# Cleanroom_Nano.net
KiCad netlist of a schematic drawn in EAGLE
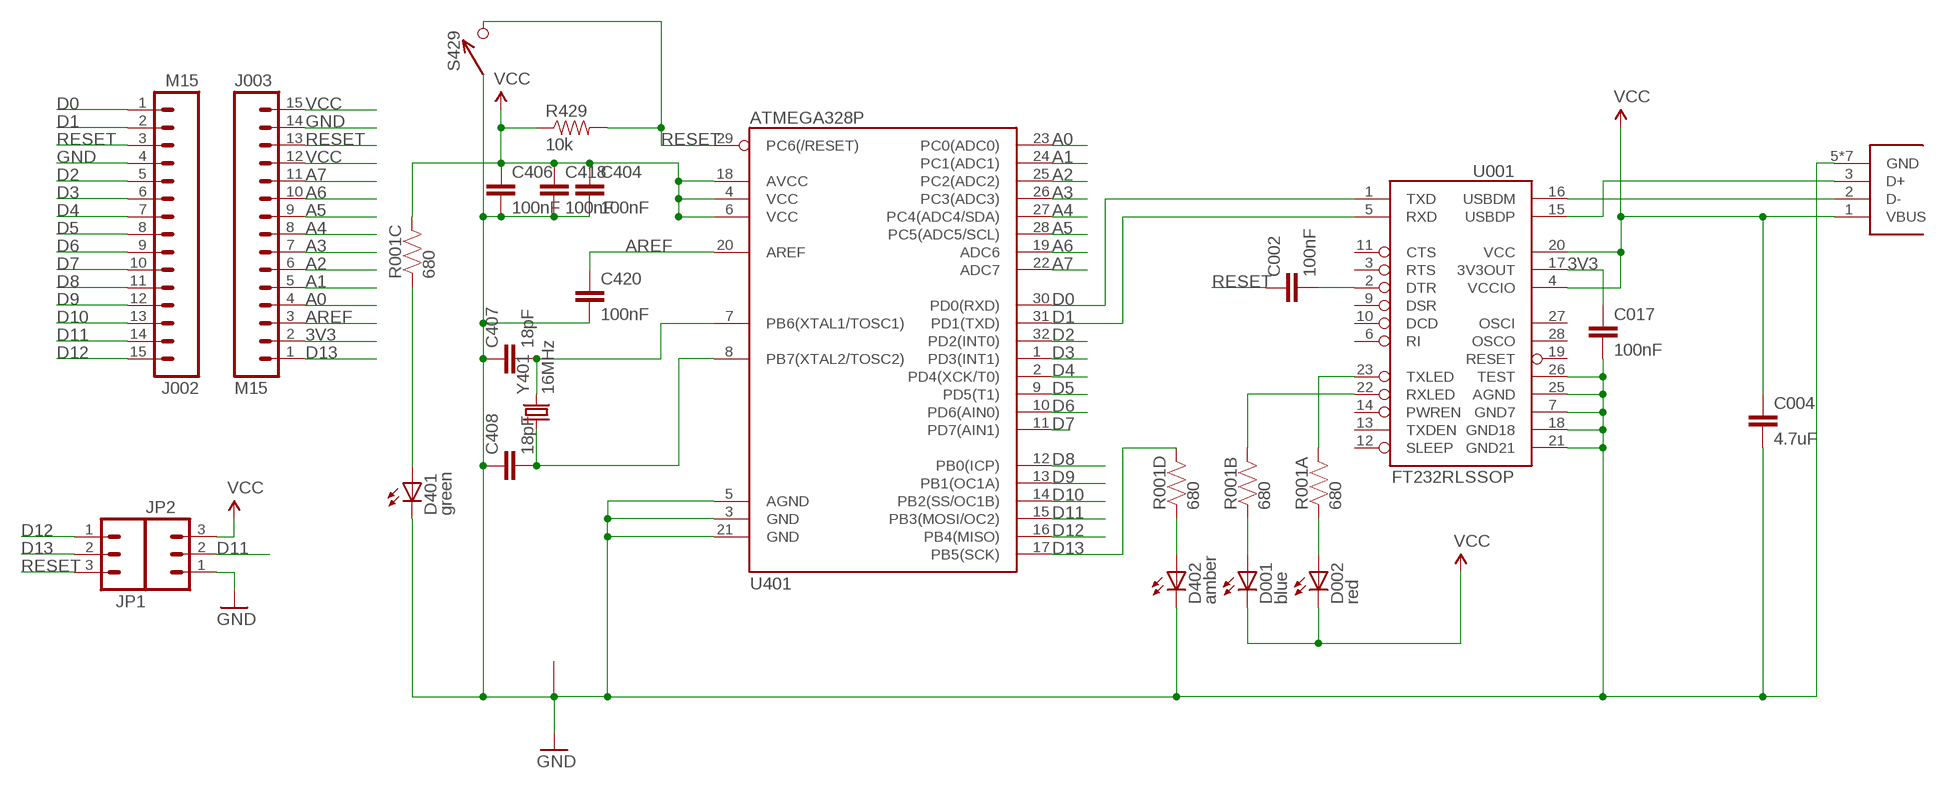
[diagram p0: schematic, sheet 1]

(export (version "E")
  (design (tool "Eeschema 10.0.6"))
  (components
    (comp (ref "C002")
      (value "100nF")
      (footprint "eagle-import:0402-CAP")
      (libsource (lib "eagle-import") (part "CAP0402-CAP"))
    )
    (comp (ref "C004")
      (value "4.7uF")
      (footprint "eagle-import:0402-CAP")
      (libsource (lib "eagle-import") (part "CAP0402-CAP"))
    )
    (comp (ref "C017")
      (value "100nF")
      (footprint "eagle-import:0402-CAP")
      (libsource (lib "eagle-import") (part "CAP0402-CAP"))
    )
    (comp (ref "C404")
      (value "100nF")
      (footprint "eagle-import:0402-CAP")
      (libsource (lib "eagle-import") (part "CAP0402-CAP"))
    )
    (comp (ref "C406")
      (value "100nF")
      (footprint "eagle-import:0402-CAP")
      (libsource (lib "eagle-import") (part "CAP0402-CAP"))
    )
    (comp (ref "C407")
      (value "18pF")
      (footprint "eagle-import:0402-CAP")
      (libsource (lib "eagle-import") (part "CAP0402-CAP"))
    )
    (comp (ref "C408")
      (value "18pF")
      (footprint "eagle-import:0402-CAP")
      (libsource (lib "eagle-import") (part "CAP0402-CAP"))
    )
    (comp (ref "C418")
      (value "100nF")
      (footprint "eagle-import:0402-CAP")
      (libsource (lib "eagle-import") (part "CAP0402-CAP"))
    )
    (comp (ref "C420")
      (value "100nF")
      (footprint "eagle-import:0402-CAP")
      (libsource (lib "eagle-import") (part "CAP0402-CAP"))
    )
    (comp (ref "D001")
      (value "blue")
      (footprint "eagle-import:LED-0603")
      (libsource (lib "eagle-import") (part "LED0603"))
    )
    (comp (ref "D002")
      (value "red")
      (footprint "eagle-import:LED-0603")
      (libsource (lib "eagle-import") (part "LED0603"))
    )
    (comp (ref "D401")
      (value "green")
      (footprint "eagle-import:LED-0603")
      (libsource (lib "eagle-import") (part "LED0603"))
    )
    (comp (ref "D402")
      (value "amber")
      (footprint "eagle-import:LED-0603")
      (libsource (lib "eagle-import") (part "LED0603"))
    )
    (comp (ref "J001")
      (value "USB_MICROB_JST")
      (footprint "eagle-import:UB-MC5BR3-SD204-4S")
      (libsource (lib "eagle-import") (part "USB_MICROB_JST"))
    )
    (comp (ref "J002")
      (value "M15")
      (footprint "eagle-import:1X15")
      (libsource (lib "eagle-import") (part "M15"))
    )
    (comp (ref "J003")
      (value "M15")
      (footprint "eagle-import:1X15")
      (libsource (lib "eagle-import") (part "M15"))
    )
    (comp (ref "JP1")
      (value "M03PTH")
      (footprint "eagle-import:1X03")
      (libsource (lib "eagle-import") (part "M03PTH"))
    )
    (comp (ref "JP2")
      (value "M03PTH")
      (footprint "eagle-import:1X03")
      (libsource (lib "eagle-import") (part "M03PTH"))
    )
    (comp (ref "R001")
      (value "680")
      (footprint "eagle-import:CRA04")
      (libsource (lib "eagle-import") (part "RP404"))
    )
    (comp (ref "R429")
      (value "10k")
      (footprint "eagle-import:0402-RES")
      (libsource (lib "eagle-import") (part "RESISTOR0402-RES"))
    )
    (comp (ref "S429")
      (value "B3U-1000P")
      (footprint "eagle-import:B3U-1000P")
      (libsource (lib "eagle-import") (part "B3U-1000P"))
    )
    (comp (ref "U001")
      (value "FT232RLSSOP")
      (footprint "eagle-import:SSOP28DB")
      (libsource (lib "eagle-import") (part "FT232RLSSOP"))
    )
    (comp (ref "U401")
      (value "ATMEGA328P")
      (footprint "eagle-import:TQFP32-08")
      (libsource (lib "eagle-import") (part "ATMEGA168"))
    )
    (comp (ref "Y401")
      (value "16MHz")
      (footprint "eagle-import:CRYSTAL_SMD_2MM_2_5MM")
      (libsource (lib "eagle-import") (part "CX2520"))
    )
  )
  (nets
    (net (code "1") (name "/3V3") (class "Default")
      (node (ref "C017") (pin "1") (pinfunction "1_1") (pintype "passive"))
      (node (ref "J003") (pin "2") (pinfunction "2_2") (pintype "passive"))
      (node (ref "U001") (pin "17") (pinfunction "3V3OUT_17") (pintype "output"))
    )
    (net (code "2") (name "/A0") (class "Default")
      (node (ref "J003") (pin "4") (pinfunction "4_4") (pintype "passive"))
      (node (ref "U401") (pin "23") (pinfunction "PC0(ADC0)_23") (pintype "bidirectional"))
    )
    (net (code "3") (name "/A1") (class "Default")
      (node (ref "J003") (pin "5") (pinfunction "5_5") (pintype "passive"))
      (node (ref "U401") (pin "24") (pinfunction "PC1(ADC1)_24") (pintype "bidirectional"))
    )
    (net (code "4") (name "/A2") (class "Default")
      (node (ref "J003") (pin "6") (pinfunction "6_6") (pintype "passive"))
      (node (ref "U401") (pin "25") (pinfunction "PC2(ADC2)_25") (pintype "bidirectional"))
    )
    (net (code "5") (name "/A3") (class "Default")
      (node (ref "J003") (pin "7") (pinfunction "7_7") (pintype "passive"))
      (node (ref "U401") (pin "26") (pinfunction "PC3(ADC3)_26") (pintype "bidirectional"))
    )
    (net (code "6") (name "/A4") (class "Default")
      (node (ref "J003") (pin "8") (pinfunction "8_8") (pintype "passive"))
      (node (ref "U401") (pin "27") (pinfunction "PC4(ADC4/SDA)_27") (pintype "bidirectional"))
    )
    (net (code "7") (name "/A5") (class "Default")
      (node (ref "J003") (pin "9") (pinfunction "9_9") (pintype "passive"))
      (node (ref "U401") (pin "28") (pinfunction "PC5(ADC5/SCL)_28") (pintype "bidirectional"))
    )
    (net (code "8") (name "/A6") (class "Default")
      (node (ref "J003") (pin "10") (pinfunction "10_10") (pintype "passive"))
      (node (ref "U401") (pin "19") (pinfunction "ADC6_19") (pintype "bidirectional"))
    )
    (net (code "9") (name "/A7") (class "Default")
      (node (ref "J003") (pin "11") (pinfunction "11_11") (pintype "passive"))
      (node (ref "U401") (pin "22") (pinfunction "ADC7_22") (pintype "bidirectional"))
    )
    (net (code "10") (name "/AREF") (class "Default")
      (node (ref "C420") (pin "1") (pinfunction "1_1") (pintype "passive"))
      (node (ref "J003") (pin "3") (pinfunction "3_3") (pintype "passive"))
      (node (ref "U401") (pin "20") (pinfunction "AREF_20") (pintype "bidirectional"))
    )
    (net (code "11") (name "/D0") (class "Default")
      (node (ref "J002") (pin "1") (pinfunction "1_1") (pintype "passive"))
      (node (ref "U001") (pin "1") (pinfunction "TXD_1") (pintype "output"))
      (node (ref "U401") (pin "30") (pinfunction "PD0(RXD)_30") (pintype "bidirectional"))
    )
    (net (code "12") (name "/D1") (class "Default")
      (node (ref "J002") (pin "2") (pinfunction "2_2") (pintype "passive"))
      (node (ref "U001") (pin "5") (pinfunction "RXD_5") (pintype "input"))
      (node (ref "U401") (pin "31") (pinfunction "PD1(TXD)_31") (pintype "bidirectional"))
    )
    (net (code "13") (name "/D2") (class "Default")
      (node (ref "J002") (pin "5") (pinfunction "5_5") (pintype "passive"))
      (node (ref "U401") (pin "32") (pinfunction "PD2(INT0)_32") (pintype "bidirectional"))
    )
    (net (code "14") (name "/D3") (class "Default")
      (node (ref "J002") (pin "6") (pinfunction "6_6") (pintype "passive"))
      (node (ref "U401") (pin "1") (pinfunction "PD3(INT1)_1") (pintype "bidirectional"))
    )
    (net (code "15") (name "/D4") (class "Default")
      (node (ref "J002") (pin "7") (pinfunction "7_7") (pintype "passive"))
      (node (ref "U401") (pin "2") (pinfunction "PD4(XCK/T0)_2") (pintype "bidirectional"))
    )
    (net (code "16") (name "/D5") (class "Default")
      (node (ref "J002") (pin "8") (pinfunction "8_8") (pintype "passive"))
      (node (ref "U401") (pin "9") (pinfunction "PD5(T1)_9") (pintype "bidirectional"))
    )
    (net (code "17") (name "/D6") (class "Default")
      (node (ref "J002") (pin "9") (pinfunction "9_9") (pintype "passive"))
      (node (ref "U401") (pin "10") (pinfunction "PD6(AIN0)_10") (pintype "bidirectional"))
    )
    (net (code "18") (name "/D7") (class "Default")
      (node (ref "J002") (pin "10") (pinfunction "10_10") (pintype "passive"))
      (node (ref "U401") (pin "11") (pinfunction "PD7(AIN1)_11") (pintype "bidirectional"))
    )
    (net (code "19") (name "/D8") (class "Default")
      (node (ref "J002") (pin "11") (pinfunction "11_11") (pintype "passive"))
      (node (ref "U401") (pin "12") (pinfunction "PB0(ICP)_12") (pintype "bidirectional"))
    )
    (net (code "20") (name "/D9") (class "Default")
      (node (ref "J002") (pin "12") (pinfunction "12_12") (pintype "passive"))
      (node (ref "U401") (pin "13") (pinfunction "PB1(OC1A)_13") (pintype "bidirectional"))
    )
    (net (code "21") (name "/D10") (class "Default")
      (node (ref "J002") (pin "13") (pinfunction "13_13") (pintype "passive"))
      (node (ref "U401") (pin "14") (pinfunction "PB2(SS/OC1B)_14") (pintype "bidirectional"))
    )
    (net (code "22") (name "/D11") (class "Default")
      (node (ref "J002") (pin "14") (pinfunction "14_14") (pintype "passive"))
      (node (ref "JP2") (pin "2") (pinfunction "2_2") (pintype "passive"))
      (node (ref "U401") (pin "15") (pinfunction "PB3(MOSI/OC2)_15") (pintype "bidirectional"))
    )
    (net (code "23") (name "/D12") (class "Default")
      (node (ref "J002") (pin "15") (pinfunction "15_15") (pintype "passive"))
      (node (ref "JP1") (pin "1") (pinfunction "1_1") (pintype "passive"))
      (node (ref "U401") (pin "16") (pinfunction "PB4(MISO)_16") (pintype "bidirectional"))
    )
    (net (code "24") (name "/D13") (class "Default")
      (node (ref "J003") (pin "1") (pinfunction "1_1") (pintype "passive"))
      (node (ref "JP1") (pin "2") (pinfunction "2_2") (pintype "passive"))
      (node (ref "R001") (pin "5") (pinfunction "2_5") (pintype "passive"))
      (node (ref "U401") (pin "17") (pinfunction "PB5(SCK)_17") (pintype "bidirectional"))
    )
    (net (code "25") (name "/RESET") (class "Default")
      (node (ref "C002") (pin "1") (pinfunction "1_1") (pintype "passive"))
      (node (ref "J002") (pin "3") (pinfunction "3_3") (pintype "passive"))
      (node (ref "J003") (pin "13") (pinfunction "13_13") (pintype "passive"))
      (node (ref "JP1") (pin "3") (pinfunction "3_3") (pintype "passive"))
      (node (ref "R429") (pin "2") (pinfunction "2_2") (pintype "passive"))
      (node (ref "S429") (pin "P$2") (pinfunction "2_P$2") (pintype "bidirectional"))
      (node (ref "U401") (pin "29") (pinfunction "PC6(/RESET)_29") (pintype "bidirectional"))
    )
    (net (code "26") (name "GND") (class "Default")
      (node (ref "C004") (pin "2") (pinfunction "2_2") (pintype "passive"))
      (node (ref "C017") (pin "2") (pinfunction "2_2") (pintype "passive"))
      (node (ref "C404") (pin "2") (pinfunction "2_2") (pintype "passive"))
      (node (ref "C406") (pin "2") (pinfunction "2_2") (pintype "passive"))
      (node (ref "C407") (pin "1") (pinfunction "1_1") (pintype "passive"))
      (node (ref "C408") (pin "1") (pinfunction "1_1") (pintype "passive"))
      (node (ref "C418") (pin "2") (pinfunction "2_2") (pintype "passive"))
      (node (ref "C420") (pin "2") (pinfunction "2_2") (pintype "passive"))
      (node (ref "D401") (pin "C") (pinfunction "C_C") (pintype "passive"))
      (node (ref "D402") (pin "C") (pinfunction "C_C") (pintype "passive"))
      (node (ref "J001") (pin "5") (pinfunction "GND_5") (pintype "bidirectional"))
      (node (ref "J001") (pin "P$10") (pinfunction "GND_P$10") (pintype "bidirectional"))
      (node (ref "J001") (pin "P$11") (pinfunction "GND_P$11") (pintype "bidirectional"))
      (node (ref "J001") (pin "P$6") (pinfunction "GND_P$6") (pintype "bidirectional"))
      (node (ref "J001") (pin "P$7") (pinfunction "GND_P$7") (pintype "bidirectional"))
      (node (ref "J001") (pin "P$8") (pinfunction "GND_P$8") (pintype "bidirectional"))
      (node (ref "J001") (pin "P$9") (pinfunction "GND_P$9") (pintype "bidirectional"))
      (node (ref "J002") (pin "4") (pinfunction "4_4") (pintype "passive"))
      (node (ref "J003") (pin "14") (pinfunction "14_14") (pintype "passive"))
      (node (ref "JP2") (pin "1") (pinfunction "1_1") (pintype "passive"))
      (node (ref "S429") (pin "P$1") (pinfunction "1_P$1") (pintype "bidirectional"))
      (node (ref "U001") (pin "18") (pinfunction "GND18_18") (pintype "power_in"))
      (node (ref "U001") (pin "21") (pinfunction "GND21_21") (pintype "power_in"))
      (node (ref "U001") (pin "25") (pinfunction "AGND_25") (pintype "power_in"))
      (node (ref "U001") (pin "26") (pinfunction "TEST_26") (pintype "input"))
      (node (ref "U001") (pin "7") (pinfunction "GND7_7") (pintype "power_in"))
      (node (ref "U401") (pin "21") (pinfunction "GND_21") (pintype "bidirectional"))
      (node (ref "U401") (pin "3") (pinfunction "GND_3") (pintype "bidirectional"))
      (node (ref "U401") (pin "5") (pinfunction "AGND_5") (pintype "bidirectional"))
      (node (ref "Y401") (pin "2") (pinfunction "1_2") (pintype "bidirectional"))
      (node (ref "Y401") (pin "4") (pinfunction "1_4") (pintype "bidirectional"))
    )
    (net (code "27") (name "Net-(D002-PadA)") (class "Default")
      (node (ref "D002") (pin "A") (pinfunction "A_A") (pintype "passive"))
      (node (ref "R001") (pin "1") (pinfunction "1_1") (pintype "passive"))
    )
    (net (code "28") (name "Net-(J001-D+)") (class "Default")
      (node (ref "J001") (pin "3") (pinfunction "D+_3") (pintype "bidirectional"))
      (node (ref "U001") (pin "15") (pinfunction "USBDP_15") (pintype "bidirectional"))
    )
    (net (code "29") (name "Net-(J001-D-)") (class "Default")
      (node (ref "J001") (pin "2") (pinfunction "D-_2") (pintype "bidirectional"))
      (node (ref "U001") (pin "16") (pinfunction "USBDM_16") (pintype "bidirectional"))
    )
    (net (code "30") (name "Net-(R001A-2)") (class "Default")
      (node (ref "R001") (pin "8") (pinfunction "2_8") (pintype "passive"))
      (node (ref "U001") (pin "23") (pinfunction "TXLED_23") (pintype "input"))
    )
    (net (code "31") (name "Net-(R001B-1)") (class "Default")
      (node (ref "D001") (pin "A") (pinfunction "A_A") (pintype "passive"))
      (node (ref "R001") (pin "2") (pinfunction "1_2") (pintype "passive"))
    )
    (net (code "32") (name "Net-(R001B-2)") (class "Default")
      (node (ref "R001") (pin "7") (pinfunction "2_7") (pintype "passive"))
      (node (ref "U001") (pin "22") (pinfunction "RXLED_22") (pintype "input"))
    )
    (net (code "33") (name "Net-(R001C-1)") (class "Default")
      (node (ref "D401") (pin "A") (pinfunction "A_A") (pintype "passive"))
      (node (ref "R001") (pin "3") (pinfunction "1_3") (pintype "passive"))
    )
    (net (code "34") (name "Net-(R001D-1)") (class "Default")
      (node (ref "D402") (pin "A") (pinfunction "A_A") (pintype "passive"))
      (node (ref "R001") (pin "4") (pinfunction "1_4") (pintype "passive"))
    )
    (net (code "35") (name "Net-(U001-DTR)") (class "Default")
      (node (ref "C002") (pin "2") (pinfunction "2_2") (pintype "passive"))
      (node (ref "U001") (pin "2") (pinfunction "DTR_2") (pintype "output"))
    )
    (net (code "36") (name "Net-(U401-PB6(XTAL1{slash}TOSC1))") (class "Default")
      (node (ref "C407") (pin "2") (pinfunction "2_2") (pintype "passive"))
      (node (ref "U401") (pin "7") (pinfunction "PB6(XTAL1/TOSC1)_7") (pintype "bidirectional"))
      (node (ref "Y401") (pin "3") (pinfunction "2_3") (pintype "passive"))
    )
    (net (code "37") (name "Net-(U401-PB7(XTAL2{slash}TOSC2))") (class "Default")
      (node (ref "C408") (pin "2") (pinfunction "2_2") (pintype "passive"))
      (node (ref "U401") (pin "8") (pinfunction "PB7(XTAL2/TOSC2)_8") (pintype "bidirectional"))
      (node (ref "Y401") (pin "1") (pinfunction "1_1") (pintype "passive"))
    )
    (net (code "38") (name "VCC") (class "Default")
      (node (ref "C004") (pin "1") (pinfunction "1_1") (pintype "passive"))
      (node (ref "C404") (pin "1") (pinfunction "1_1") (pintype "passive"))
      (node (ref "C406") (pin "1") (pinfunction "1_1") (pintype "passive"))
      (node (ref "C418") (pin "1") (pinfunction "1_1") (pintype "passive"))
      (node (ref "D001") (pin "C") (pinfunction "C_C") (pintype "passive"))
      (node (ref "D002") (pin "C") (pinfunction "C_C") (pintype "passive"))
      (node (ref "J001") (pin "1") (pinfunction "VBUS_1") (pintype "bidirectional"))
      (node (ref "J003") (pin "12") (pinfunction "12_12") (pintype "passive"))
      (node (ref "J003") (pin "15") (pinfunction "15_15") (pintype "passive"))
      (node (ref "JP2") (pin "3") (pinfunction "3_3") (pintype "passive"))
      (node (ref "R001") (pin "6") (pinfunction "2_6") (pintype "passive"))
      (node (ref "R429") (pin "1") (pinfunction "1_1") (pintype "passive"))
      (node (ref "U001") (pin "20") (pinfunction "VCC_20") (pintype "power_in"))
      (node (ref "U001") (pin "4") (pinfunction "VCCIO_4") (pintype "power_in"))
      (node (ref "U401") (pin "18") (pinfunction "AVCC_18") (pintype "bidirectional"))
      (node (ref "U401") (pin "4") (pinfunction "VCC_4") (pintype "bidirectional"))
      (node (ref "U401") (pin "6") (pinfunction "VCC_6") (pintype "bidirectional"))
    )
    (net (code "39") (name "unconnected-(U001-CTS-Pad11)") (class "Default")
      (node (ref "U001") (pin "11") (pinfunction "CTS_11") (pintype "input"))
    )
    (net (code "40") (name "unconnected-(U001-DCD-Pad10)") (class "Default")
      (node (ref "U001") (pin "10") (pinfunction "DCD_10") (pintype "input"))
    )
    (net (code "41") (name "unconnected-(U001-DSR-Pad9)") (class "Default")
      (node (ref "U001") (pin "9") (pinfunction "DSR_9") (pintype "input"))
    )
    (net (code "42") (name "unconnected-(U001-OSCI-Pad27)") (class "Default")
      (node (ref "U001") (pin "27") (pinfunction "OSCI_27") (pintype "input"))
    )
    (net (code "43") (name "unconnected-(U001-OSCO-Pad28)") (class "Default")
      (node (ref "U001") (pin "28") (pinfunction "OSCO_28") (pintype "output"))
    )
    (net (code "44") (name "unconnected-(U001-PWREN-Pad14)") (class "Default")
      (node (ref "U001") (pin "14") (pinfunction "PWREN_14") (pintype "input"))
    )
    (net (code "45") (name "unconnected-(U001-RESET-Pad19)") (class "Default")
      (node (ref "U001") (pin "19") (pinfunction "RESET_19") (pintype "input"))
    )
    (net (code "46") (name "unconnected-(U001-RI-Pad6)") (class "Default")
      (node (ref "U001") (pin "6") (pinfunction "RI_6") (pintype "input"))
    )
    (net (code "47") (name "unconnected-(U001-RTS-Pad3)") (class "Default")
      (node (ref "U001") (pin "3") (pinfunction "RTS_3") (pintype "output"))
    )
    (net (code "48") (name "unconnected-(U001-SLEEP-Pad12)") (class "Default")
      (node (ref "U001") (pin "12") (pinfunction "SLEEP_12") (pintype "input"))
    )
    (net (code "49") (name "unconnected-(U001-TXDEN-Pad13)") (class "Default")
      (node (ref "U001") (pin "13") (pinfunction "TXDEN_13") (pintype "input"))
    )
  )
)
